# Callisto_Teknic_MSO_PBx4_v1p3.net
KiCad netlist of a schematic drawn in EAGLE
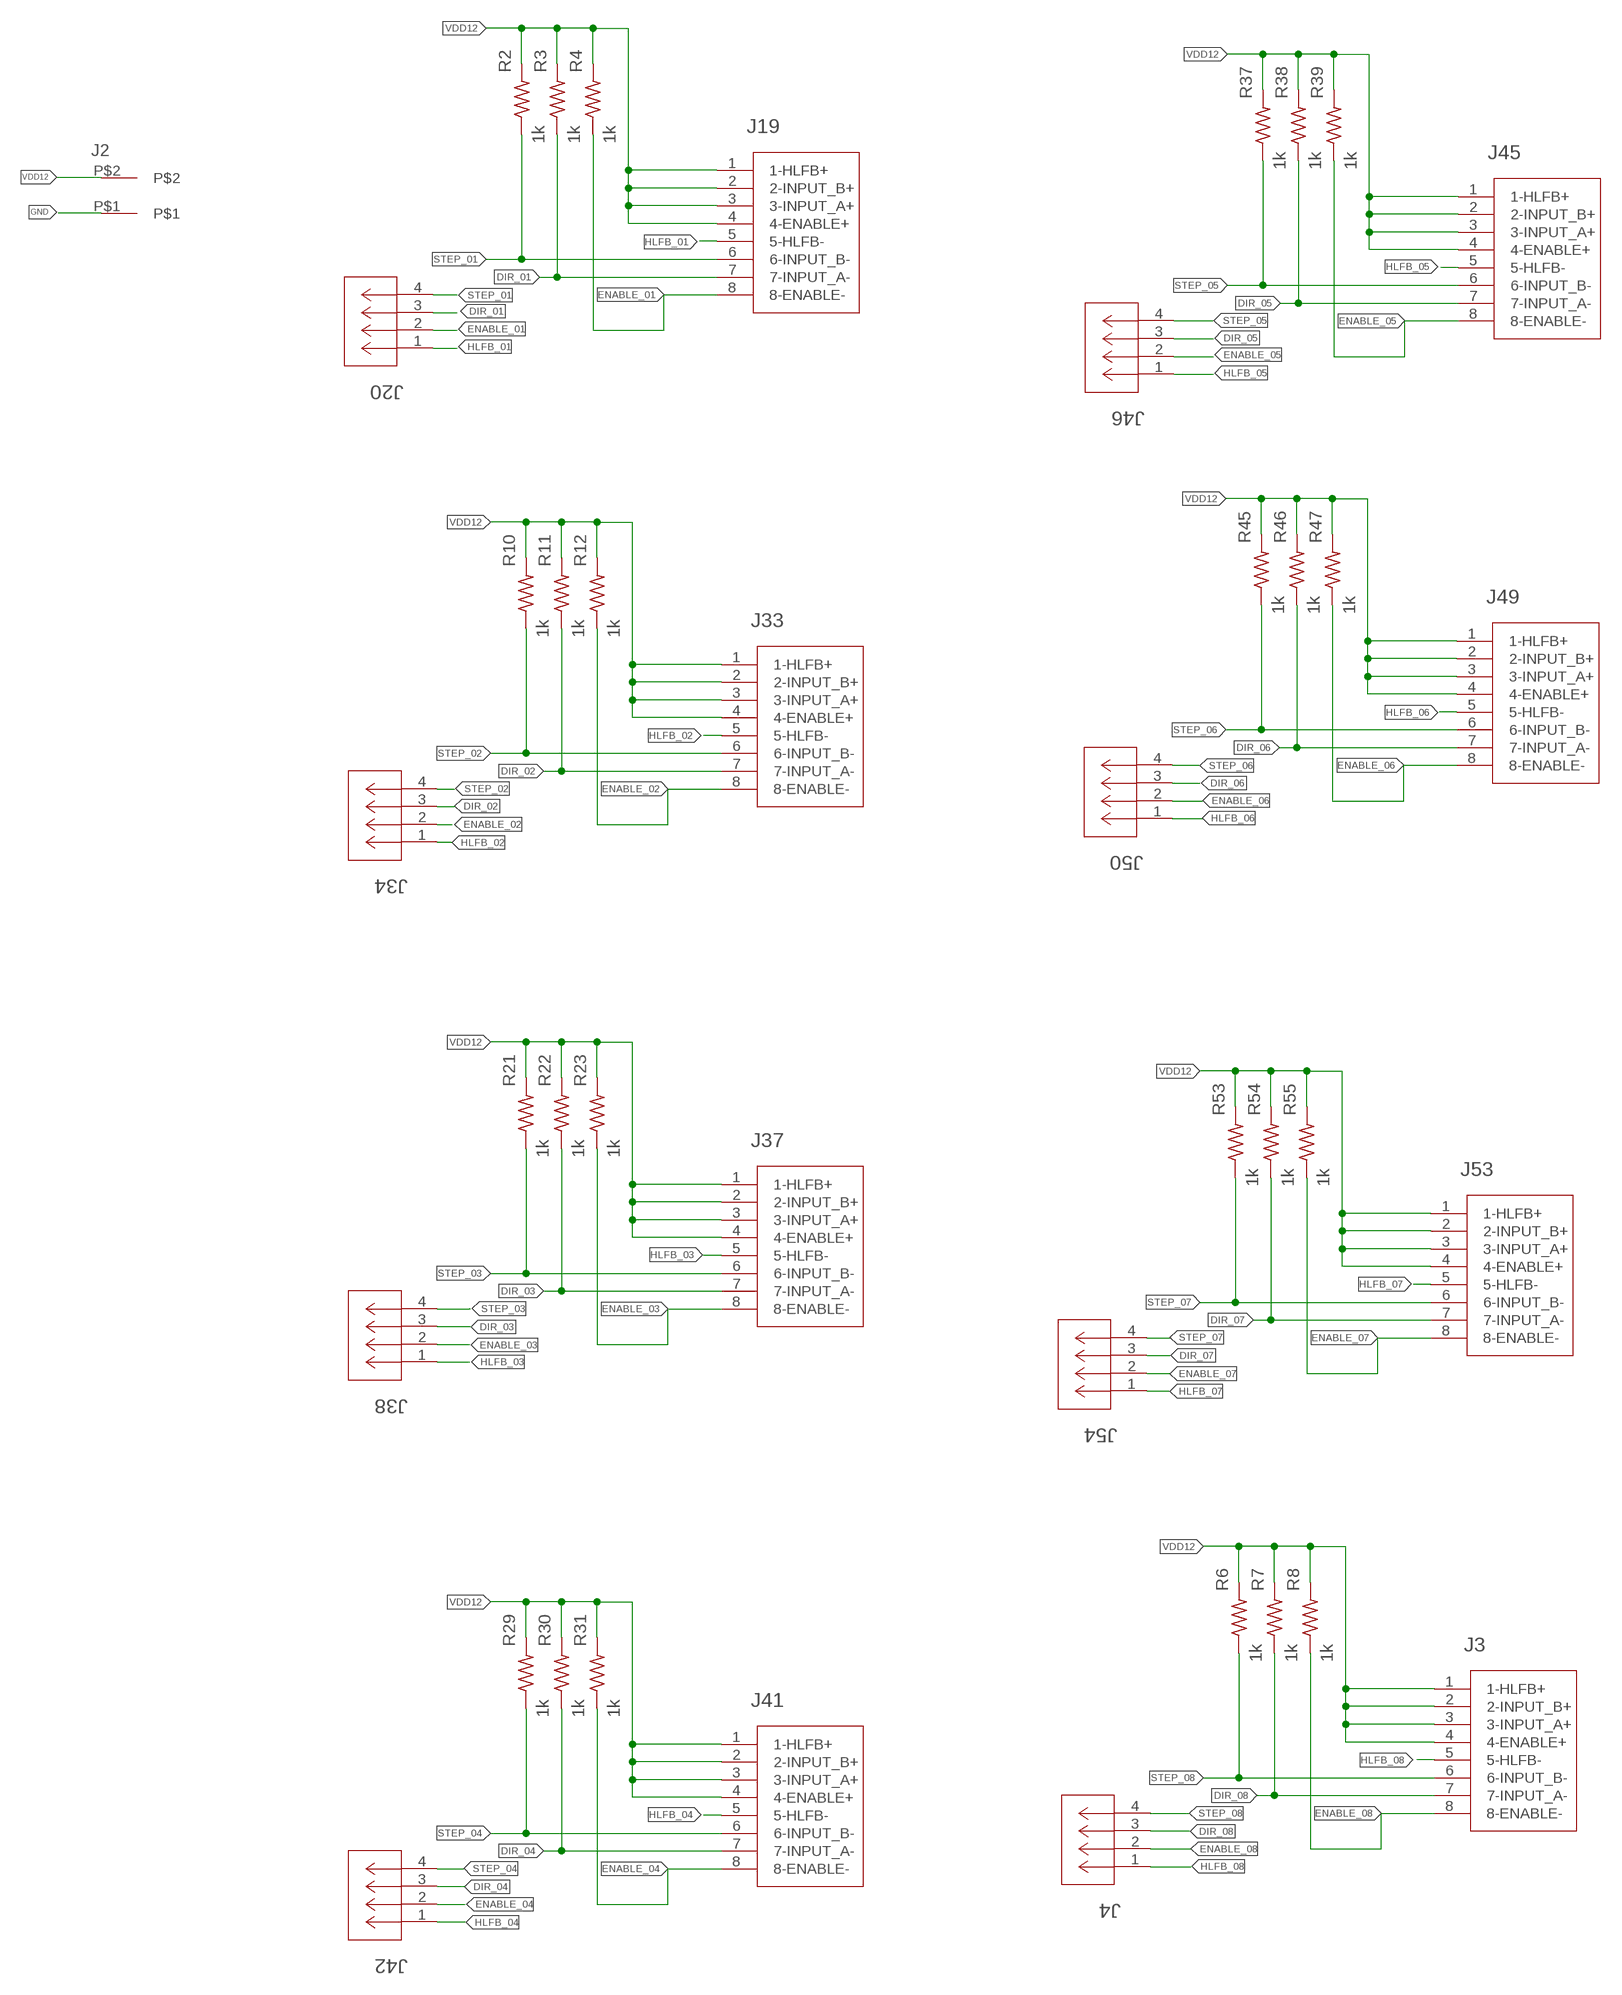
[diagram p0: schematic, sheet 1]

(export (version "E")
  (design (tool "Eeschema 10.0.6"))
  (components
    (comp (ref "J2")
      (value "2-pos")
      (footprint "eagle-import:2_3.81MM_PITCH")
      (fields (field (name "PARTNO") "691322310002"))
      (libsource (lib "eagle-import") (part "3.81MM_1_X_2_RT_ANGLE_PLUG_HEADER"))
    )
    (comp (ref "J3")
      (value "TEKNIC_8PIN_MOTOR")
      (footprint "eagle-import:CON_39281083")
      (fields
        (field (name "MANUFACTURER_PART_NUMBER") "39281083")
        (field (name "COPYRIGHT") "Copyright (C) 2022 Ultra Librarian. All rights reserved.")
      )
      (libsource (lib "eagle-import") (part "TEKNIC_8PIN_MOTOR"))
    )
    (comp (ref "J4")
      (value "CONN_530470410_PICOBLADE_X_4")
      (footprint "eagle-import:CON_530470410_MOL")
      (fields
        (field (name "MANUFACTURER_PART_NUMBER") "530470410")
        (field (name "COPYRIGHT") "Copyright (C) 2022 Ultra Librarian. All rights reserved.")
      )
      (libsource (lib "eagle-import") (part "CONN_530470410_PICOBLADE_X_4"))
    )
    (comp (ref "J19")
      (value "TEKNIC_8PIN_MOTOR")
      (footprint "eagle-import:CON_39281083")
      (fields
        (field (name "MANUFACTURER_PART_NUMBER") "39281083")
        (field (name "COPYRIGHT") "Copyright (C) 2022 Ultra Librarian. All rights reserved.")
      )
      (libsource (lib "eagle-import") (part "TEKNIC_8PIN_MOTOR"))
    )
    (comp (ref "J20")
      (value "CONN_530470410_PICOBLADE_X_4")
      (footprint "eagle-import:CON_530470410_MOL")
      (fields
        (field (name "MANUFACTURER_PART_NUMBER") "530470410")
        (field (name "COPYRIGHT") "Copyright (C) 2022 Ultra Librarian. All rights reserved.")
      )
      (libsource (lib "eagle-import") (part "CONN_530470410_PICOBLADE_X_4"))
    )
    (comp (ref "J33")
      (value "TEKNIC_8PIN_MOTOR")
      (footprint "eagle-import:CON_39281083")
      (fields
        (field (name "MANUFACTURER_PART_NUMBER") "39281083")
        (field (name "COPYRIGHT") "Copyright (C) 2022 Ultra Librarian. All rights reserved.")
      )
      (libsource (lib "eagle-import") (part "TEKNIC_8PIN_MOTOR"))
    )
    (comp (ref "J34")
      (value "CONN_530470410_PICOBLADE_X_4")
      (footprint "eagle-import:CON_530470410_MOL")
      (fields
        (field (name "MANUFACTURER_PART_NUMBER") "530470410")
        (field (name "COPYRIGHT") "Copyright (C) 2022 Ultra Librarian. All rights reserved.")
      )
      (libsource (lib "eagle-import") (part "CONN_530470410_PICOBLADE_X_4"))
    )
    (comp (ref "J37")
      (value "TEKNIC_8PIN_MOTOR")
      (footprint "eagle-import:CON_39281083")
      (fields
        (field (name "MANUFACTURER_PART_NUMBER") "39281083")
        (field (name "COPYRIGHT") "Copyright (C) 2022 Ultra Librarian. All rights reserved.")
      )
      (libsource (lib "eagle-import") (part "TEKNIC_8PIN_MOTOR"))
    )
    (comp (ref "J38")
      (value "CONN_530470410_PICOBLADE_X_4")
      (footprint "eagle-import:CON_530470410_MOL")
      (fields
        (field (name "MANUFACTURER_PART_NUMBER") "530470410")
        (field (name "COPYRIGHT") "Copyright (C) 2022 Ultra Librarian. All rights reserved.")
      )
      (libsource (lib "eagle-import") (part "CONN_530470410_PICOBLADE_X_4"))
    )
    (comp (ref "J41")
      (value "TEKNIC_8PIN_MOTOR")
      (footprint "eagle-import:CON_39281083")
      (fields
        (field (name "MANUFACTURER_PART_NUMBER") "39281083")
        (field (name "COPYRIGHT") "Copyright (C) 2022 Ultra Librarian. All rights reserved.")
      )
      (libsource (lib "eagle-import") (part "TEKNIC_8PIN_MOTOR"))
    )
    (comp (ref "J42")
      (value "CONN_530470410_PICOBLADE_X_4")
      (footprint "eagle-import:CON_530470410_MOL")
      (fields
        (field (name "MANUFACTURER_PART_NUMBER") "530470410")
        (field (name "COPYRIGHT") "Copyright (C) 2022 Ultra Librarian. All rights reserved.")
      )
      (libsource (lib "eagle-import") (part "CONN_530470410_PICOBLADE_X_4"))
    )
    (comp (ref "J45")
      (value "TEKNIC_8PIN_MOTOR")
      (footprint "eagle-import:CON_39281083")
      (fields
        (field (name "MANUFACTURER_PART_NUMBER") "39281083")
        (field (name "COPYRIGHT") "Copyright (C) 2022 Ultra Librarian. All rights reserved.")
      )
      (libsource (lib "eagle-import") (part "TEKNIC_8PIN_MOTOR"))
    )
    (comp (ref "J46")
      (value "CONN_530470410_PICOBLADE_X_4")
      (footprint "eagle-import:CON_530470410_MOL")
      (fields
        (field (name "MANUFACTURER_PART_NUMBER") "530470410")
        (field (name "COPYRIGHT") "Copyright (C) 2022 Ultra Librarian. All rights reserved.")
      )
      (libsource (lib "eagle-import") (part "CONN_530470410_PICOBLADE_X_4"))
    )
    (comp (ref "J49")
      (value "TEKNIC_8PIN_MOTOR")
      (footprint "eagle-import:CON_39281083")
      (fields
        (field (name "MANUFACTURER_PART_NUMBER") "39281083")
        (field (name "COPYRIGHT") "Copyright (C) 2022 Ultra Librarian. All rights reserved.")
      )
      (libsource (lib "eagle-import") (part "TEKNIC_8PIN_MOTOR"))
    )
    (comp (ref "J50")
      (value "CONN_530470410_PICOBLADE_X_4")
      (footprint "eagle-import:CON_530470410_MOL")
      (fields
        (field (name "MANUFACTURER_PART_NUMBER") "530470410")
        (field (name "COPYRIGHT") "Copyright (C) 2022 Ultra Librarian. All rights reserved.")
      )
      (libsource (lib "eagle-import") (part "CONN_530470410_PICOBLADE_X_4"))
    )
    (comp (ref "J53")
      (value "TEKNIC_8PIN_MOTOR")
      (footprint "eagle-import:CON_39281083")
      (fields
        (field (name "MANUFACTURER_PART_NUMBER") "39281083")
        (field (name "COPYRIGHT") "Copyright (C) 2022 Ultra Librarian. All rights reserved.")
      )
      (libsource (lib "eagle-import") (part "TEKNIC_8PIN_MOTOR"))
    )
    (comp (ref "J54")
      (value "CONN_530470410_PICOBLADE_X_4")
      (footprint "eagle-import:CON_530470410_MOL")
      (fields
        (field (name "MANUFACTURER_PART_NUMBER") "530470410")
        (field (name "COPYRIGHT") "Copyright (C) 2022 Ultra Librarian. All rights reserved.")
      )
      (libsource (lib "eagle-import") (part "CONN_530470410_PICOBLADE_X_4"))
    )
    (comp (ref "R2")
      (value "1k")
      (footprint "eagle-import:0805")
      (libsource (lib "eagle-import") (part "R_0805"))
    )
    (comp (ref "R3")
      (value "1k")
      (footprint "eagle-import:0805")
      (libsource (lib "eagle-import") (part "R_0805"))
    )
    (comp (ref "R4")
      (value "1k")
      (footprint "eagle-import:0805")
      (libsource (lib "eagle-import") (part "R_0805"))
    )
    (comp (ref "R6")
      (value "1k")
      (footprint "eagle-import:0805")
      (libsource (lib "eagle-import") (part "R_0805"))
    )
    (comp (ref "R7")
      (value "1k")
      (footprint "eagle-import:0805")
      (libsource (lib "eagle-import") (part "R_0805"))
    )
    (comp (ref "R8")
      (value "1k")
      (footprint "eagle-import:0805")
      (libsource (lib "eagle-import") (part "R_0805"))
    )
    (comp (ref "R10")
      (value "1k")
      (footprint "eagle-import:0805")
      (libsource (lib "eagle-import") (part "R_0805"))
    )
    (comp (ref "R11")
      (value "1k")
      (footprint "eagle-import:0805")
      (libsource (lib "eagle-import") (part "R_0805"))
    )
    (comp (ref "R12")
      (value "1k")
      (footprint "eagle-import:0805")
      (libsource (lib "eagle-import") (part "R_0805"))
    )
    (comp (ref "R21")
      (value "1k")
      (footprint "eagle-import:0805")
      (libsource (lib "eagle-import") (part "R_0805"))
    )
    (comp (ref "R22")
      (value "1k")
      (footprint "eagle-import:0805")
      (libsource (lib "eagle-import") (part "R_0805"))
    )
    (comp (ref "R23")
      (value "1k")
      (footprint "eagle-import:0805")
      (libsource (lib "eagle-import") (part "R_0805"))
    )
    (comp (ref "R29")
      (value "1k")
      (footprint "eagle-import:0805")
      (libsource (lib "eagle-import") (part "R_0805"))
    )
    (comp (ref "R30")
      (value "1k")
      (footprint "eagle-import:0805")
      (libsource (lib "eagle-import") (part "R_0805"))
    )
    (comp (ref "R31")
      (value "1k")
      (footprint "eagle-import:0805")
      (libsource (lib "eagle-import") (part "R_0805"))
    )
    (comp (ref "R37")
      (value "1k")
      (footprint "eagle-import:0805")
      (libsource (lib "eagle-import") (part "R_0805"))
    )
    (comp (ref "R38")
      (value "1k")
      (footprint "eagle-import:0805")
      (libsource (lib "eagle-import") (part "R_0805"))
    )
    (comp (ref "R39")
      (value "1k")
      (footprint "eagle-import:0805")
      (libsource (lib "eagle-import") (part "R_0805"))
    )
    (comp (ref "R45")
      (value "1k")
      (footprint "eagle-import:0805")
      (libsource (lib "eagle-import") (part "R_0805"))
    )
    (comp (ref "R46")
      (value "1k")
      (footprint "eagle-import:0805")
      (libsource (lib "eagle-import") (part "R_0805"))
    )
    (comp (ref "R47")
      (value "1k")
      (footprint "eagle-import:0805")
      (libsource (lib "eagle-import") (part "R_0805"))
    )
    (comp (ref "R53")
      (value "1k")
      (footprint "eagle-import:0805")
      (libsource (lib "eagle-import") (part "R_0805"))
    )
    (comp (ref "R54")
      (value "1k")
      (footprint "eagle-import:0805")
      (libsource (lib "eagle-import") (part "R_0805"))
    )
    (comp (ref "R55")
      (value "1k")
      (footprint "eagle-import:0805")
      (libsource (lib "eagle-import") (part "R_0805"))
    )
  )
  (nets
    (net (code "1") (name "DIR_01") (class "Default")
      (node (ref "J19") (pin "7") (pinfunction "7-INPUT_A-_7") (pintype "passive"))
      (node (ref "J20") (pin "3") (pinfunction "3_3") (pintype "passive"))
      (node (ref "R3") (pin "1") (pinfunction "1_1") (pintype "passive"))
    )
    (net (code "2") (name "DIR_02") (class "Default")
      (node (ref "J33") (pin "7") (pinfunction "7-INPUT_A-_7") (pintype "passive"))
      (node (ref "J34") (pin "3") (pinfunction "3_3") (pintype "passive"))
      (node (ref "R11") (pin "1") (pinfunction "1_1") (pintype "passive"))
    )
    (net (code "3") (name "DIR_03") (class "Default")
      (node (ref "J37") (pin "7") (pinfunction "7-INPUT_A-_7") (pintype "passive"))
      (node (ref "J38") (pin "3") (pinfunction "3_3") (pintype "passive"))
      (node (ref "R22") (pin "1") (pinfunction "1_1") (pintype "passive"))
    )
    (net (code "4") (name "DIR_04") (class "Default")
      (node (ref "J41") (pin "7") (pinfunction "7-INPUT_A-_7") (pintype "passive"))
      (node (ref "J42") (pin "3") (pinfunction "3_3") (pintype "passive"))
      (node (ref "R30") (pin "1") (pinfunction "1_1") (pintype "passive"))
    )
    (net (code "5") (name "DIR_05") (class "Default")
      (node (ref "J45") (pin "7") (pinfunction "7-INPUT_A-_7") (pintype "passive"))
      (node (ref "J46") (pin "3") (pinfunction "3_3") (pintype "passive"))
      (node (ref "R38") (pin "1") (pinfunction "1_1") (pintype "passive"))
    )
    (net (code "6") (name "DIR_06") (class "Default")
      (node (ref "J49") (pin "7") (pinfunction "7-INPUT_A-_7") (pintype "passive"))
      (node (ref "J50") (pin "3") (pinfunction "3_3") (pintype "passive"))
      (node (ref "R46") (pin "1") (pinfunction "1_1") (pintype "passive"))
    )
    (net (code "7") (name "DIR_07") (class "Default")
      (node (ref "J53") (pin "7") (pinfunction "7-INPUT_A-_7") (pintype "passive"))
      (node (ref "J54") (pin "3") (pinfunction "3_3") (pintype "passive"))
      (node (ref "R54") (pin "1") (pinfunction "1_1") (pintype "passive"))
    )
    (net (code "8") (name "DIR_08") (class "Default")
      (node (ref "J3") (pin "7") (pinfunction "7-INPUT_A-_7") (pintype "passive"))
      (node (ref "J4") (pin "3") (pinfunction "3_3") (pintype "passive"))
      (node (ref "R7") (pin "1") (pinfunction "1_1") (pintype "passive"))
    )
    (net (code "9") (name "ENABLE_01") (class "Default")
      (node (ref "J19") (pin "8") (pinfunction "8-ENABLE-_8") (pintype "passive"))
      (node (ref "J20") (pin "2") (pinfunction "2_2") (pintype "passive"))
      (node (ref "R4") (pin "1") (pinfunction "1_1") (pintype "passive"))
    )
    (net (code "10") (name "ENABLE_02") (class "Default")
      (node (ref "J33") (pin "8") (pinfunction "8-ENABLE-_8") (pintype "passive"))
      (node (ref "J34") (pin "2") (pinfunction "2_2") (pintype "passive"))
      (node (ref "R12") (pin "1") (pinfunction "1_1") (pintype "passive"))
    )
    (net (code "11") (name "ENABLE_03") (class "Default")
      (node (ref "J37") (pin "8") (pinfunction "8-ENABLE-_8") (pintype "passive"))
      (node (ref "J38") (pin "2") (pinfunction "2_2") (pintype "passive"))
      (node (ref "R23") (pin "1") (pinfunction "1_1") (pintype "passive"))
    )
    (net (code "12") (name "ENABLE_04") (class "Default")
      (node (ref "J41") (pin "8") (pinfunction "8-ENABLE-_8") (pintype "passive"))
      (node (ref "J42") (pin "2") (pinfunction "2_2") (pintype "passive"))
      (node (ref "R31") (pin "1") (pinfunction "1_1") (pintype "passive"))
    )
    (net (code "13") (name "ENABLE_05") (class "Default")
      (node (ref "J45") (pin "8") (pinfunction "8-ENABLE-_8") (pintype "passive"))
      (node (ref "J46") (pin "2") (pinfunction "2_2") (pintype "passive"))
      (node (ref "R39") (pin "1") (pinfunction "1_1") (pintype "passive"))
    )
    (net (code "14") (name "ENABLE_06") (class "Default")
      (node (ref "J49") (pin "8") (pinfunction "8-ENABLE-_8") (pintype "passive"))
      (node (ref "J50") (pin "2") (pinfunction "2_2") (pintype "passive"))
      (node (ref "R47") (pin "1") (pinfunction "1_1") (pintype "passive"))
    )
    (net (code "15") (name "ENABLE_07") (class "Default")
      (node (ref "J53") (pin "8") (pinfunction "8-ENABLE-_8") (pintype "passive"))
      (node (ref "J54") (pin "2") (pinfunction "2_2") (pintype "passive"))
      (node (ref "R55") (pin "1") (pinfunction "1_1") (pintype "passive"))
    )
    (net (code "16") (name "ENABLE_08") (class "Default")
      (node (ref "J3") (pin "8") (pinfunction "8-ENABLE-_8") (pintype "passive"))
      (node (ref "J4") (pin "2") (pinfunction "2_2") (pintype "passive"))
      (node (ref "R8") (pin "1") (pinfunction "1_1") (pintype "passive"))
    )
    (net (code "17") (name "GND") (class "Default")
      (node (ref "J2") (pin "P$1") (pinfunction "P$1_P$1") (pintype "bidirectional"))
    )
    (net (code "18") (name "HLFB_01") (class "Default")
      (node (ref "J19") (pin "5") (pinfunction "5-HLFB-_5") (pintype "passive"))
      (node (ref "J20") (pin "1") (pinfunction "1_1") (pintype "passive"))
    )
    (net (code "19") (name "HLFB_02") (class "Default")
      (node (ref "J33") (pin "5") (pinfunction "5-HLFB-_5") (pintype "passive"))
      (node (ref "J34") (pin "1") (pinfunction "1_1") (pintype "passive"))
    )
    (net (code "20") (name "HLFB_03") (class "Default")
      (node (ref "J37") (pin "5") (pinfunction "5-HLFB-_5") (pintype "passive"))
      (node (ref "J38") (pin "1") (pinfunction "1_1") (pintype "passive"))
    )
    (net (code "21") (name "HLFB_04") (class "Default")
      (node (ref "J41") (pin "5") (pinfunction "5-HLFB-_5") (pintype "passive"))
      (node (ref "J42") (pin "1") (pinfunction "1_1") (pintype "passive"))
    )
    (net (code "22") (name "HLFB_05") (class "Default")
      (node (ref "J45") (pin "5") (pinfunction "5-HLFB-_5") (pintype "passive"))
      (node (ref "J46") (pin "1") (pinfunction "1_1") (pintype "passive"))
    )
    (net (code "23") (name "HLFB_06") (class "Default")
      (node (ref "J49") (pin "5") (pinfunction "5-HLFB-_5") (pintype "passive"))
      (node (ref "J50") (pin "1") (pinfunction "1_1") (pintype "passive"))
    )
    (net (code "24") (name "HLFB_07") (class "Default")
      (node (ref "J53") (pin "5") (pinfunction "5-HLFB-_5") (pintype "passive"))
      (node (ref "J54") (pin "1") (pinfunction "1_1") (pintype "passive"))
    )
    (net (code "25") (name "HLFB_08") (class "Default")
      (node (ref "J3") (pin "5") (pinfunction "5-HLFB-_5") (pintype "passive"))
      (node (ref "J4") (pin "1") (pinfunction "1_1") (pintype "passive"))
    )
    (net (code "26") (name "STEP_01") (class "Default")
      (node (ref "J19") (pin "6") (pinfunction "6-INPUT_B-_6") (pintype "passive"))
      (node (ref "J20") (pin "4") (pinfunction "4_4") (pintype "passive"))
      (node (ref "R2") (pin "1") (pinfunction "1_1") (pintype "passive"))
    )
    (net (code "27") (name "STEP_02") (class "Default")
      (node (ref "J33") (pin "6") (pinfunction "6-INPUT_B-_6") (pintype "passive"))
      (node (ref "J34") (pin "4") (pinfunction "4_4") (pintype "passive"))
      (node (ref "R10") (pin "1") (pinfunction "1_1") (pintype "passive"))
    )
    (net (code "28") (name "STEP_03") (class "Default")
      (node (ref "J37") (pin "6") (pinfunction "6-INPUT_B-_6") (pintype "passive"))
      (node (ref "J38") (pin "4") (pinfunction "4_4") (pintype "passive"))
      (node (ref "R21") (pin "1") (pinfunction "1_1") (pintype "passive"))
    )
    (net (code "29") (name "STEP_04") (class "Default")
      (node (ref "J41") (pin "6") (pinfunction "6-INPUT_B-_6") (pintype "passive"))
      (node (ref "J42") (pin "4") (pinfunction "4_4") (pintype "passive"))
      (node (ref "R29") (pin "1") (pinfunction "1_1") (pintype "passive"))
    )
    (net (code "30") (name "STEP_05") (class "Default")
      (node (ref "J45") (pin "6") (pinfunction "6-INPUT_B-_6") (pintype "passive"))
      (node (ref "J46") (pin "4") (pinfunction "4_4") (pintype "passive"))
      (node (ref "R37") (pin "1") (pinfunction "1_1") (pintype "passive"))
    )
    (net (code "31") (name "STEP_06") (class "Default")
      (node (ref "J49") (pin "6") (pinfunction "6-INPUT_B-_6") (pintype "passive"))
      (node (ref "J50") (pin "4") (pinfunction "4_4") (pintype "passive"))
      (node (ref "R45") (pin "1") (pinfunction "1_1") (pintype "passive"))
    )
    (net (code "32") (name "STEP_07") (class "Default")
      (node (ref "J53") (pin "6") (pinfunction "6-INPUT_B-_6") (pintype "passive"))
      (node (ref "J54") (pin "4") (pinfunction "4_4") (pintype "passive"))
      (node (ref "R53") (pin "1") (pinfunction "1_1") (pintype "passive"))
    )
    (net (code "33") (name "STEP_08") (class "Default")
      (node (ref "J3") (pin "6") (pinfunction "6-INPUT_B-_6") (pintype "passive"))
      (node (ref "J4") (pin "4") (pinfunction "4_4") (pintype "passive"))
      (node (ref "R6") (pin "1") (pinfunction "1_1") (pintype "passive"))
    )
    (net (code "34") (name "VDD12") (class "Default")
      (node (ref "J19") (pin "1") (pinfunction "1-HLFB+_1") (pintype "passive"))
      (node (ref "J19") (pin "2") (pinfunction "2-INPUT_B+_2") (pintype "passive"))
      (node (ref "J19") (pin "3") (pinfunction "3-INPUT_A+_3") (pintype "passive"))
      (node (ref "J19") (pin "4") (pinfunction "4-ENABLE+_4") (pintype "passive"))
      (node (ref "J2") (pin "P$2") (pinfunction "P$2_P$2") (pintype "bidirectional"))
      (node (ref "J3") (pin "1") (pinfunction "1-HLFB+_1") (pintype "passive"))
      (node (ref "J3") (pin "2") (pinfunction "2-INPUT_B+_2") (pintype "passive"))
      (node (ref "J3") (pin "3") (pinfunction "3-INPUT_A+_3") (pintype "passive"))
      (node (ref "J3") (pin "4") (pinfunction "4-ENABLE+_4") (pintype "passive"))
      (node (ref "J33") (pin "1") (pinfunction "1-HLFB+_1") (pintype "passive"))
      (node (ref "J33") (pin "2") (pinfunction "2-INPUT_B+_2") (pintype "passive"))
      (node (ref "J33") (pin "3") (pinfunction "3-INPUT_A+_3") (pintype "passive"))
      (node (ref "J33") (pin "4") (pinfunction "4-ENABLE+_4") (pintype "passive"))
      (node (ref "J37") (pin "1") (pinfunction "1-HLFB+_1") (pintype "passive"))
      (node (ref "J37") (pin "2") (pinfunction "2-INPUT_B+_2") (pintype "passive"))
      (node (ref "J37") (pin "3") (pinfunction "3-INPUT_A+_3") (pintype "passive"))
      (node (ref "J37") (pin "4") (pinfunction "4-ENABLE+_4") (pintype "passive"))
      (node (ref "J41") (pin "1") (pinfunction "1-HLFB+_1") (pintype "passive"))
      (node (ref "J41") (pin "2") (pinfunction "2-INPUT_B+_2") (pintype "passive"))
      (node (ref "J41") (pin "3") (pinfunction "3-INPUT_A+_3") (pintype "passive"))
      (node (ref "J41") (pin "4") (pinfunction "4-ENABLE+_4") (pintype "passive"))
      (node (ref "J45") (pin "1") (pinfunction "1-HLFB+_1") (pintype "passive"))
      (node (ref "J45") (pin "2") (pinfunction "2-INPUT_B+_2") (pintype "passive"))
      (node (ref "J45") (pin "3") (pinfunction "3-INPUT_A+_3") (pintype "passive"))
      (node (ref "J45") (pin "4") (pinfunction "4-ENABLE+_4") (pintype "passive"))
      (node (ref "J49") (pin "1") (pinfunction "1-HLFB+_1") (pintype "passive"))
      (node (ref "J49") (pin "2") (pinfunction "2-INPUT_B+_2") (pintype "passive"))
      (node (ref "J49") (pin "3") (pinfunction "3-INPUT_A+_3") (pintype "passive"))
      (node (ref "J49") (pin "4") (pinfunction "4-ENABLE+_4") (pintype "passive"))
      (node (ref "J53") (pin "1") (pinfunction "1-HLFB+_1") (pintype "passive"))
      (node (ref "J53") (pin "2") (pinfunction "2-INPUT_B+_2") (pintype "passive"))
      (node (ref "J53") (pin "3") (pinfunction "3-INPUT_A+_3") (pintype "passive"))
      (node (ref "J53") (pin "4") (pinfunction "4-ENABLE+_4") (pintype "passive"))
      (node (ref "R10") (pin "2") (pinfunction "2_2") (pintype "passive"))
      (node (ref "R11") (pin "2") (pinfunction "2_2") (pintype "passive"))
      (node (ref "R12") (pin "2") (pinfunction "2_2") (pintype "passive"))
      (node (ref "R2") (pin "2") (pinfunction "2_2") (pintype "passive"))
      (node (ref "R21") (pin "2") (pinfunction "2_2") (pintype "passive"))
      (node (ref "R22") (pin "2") (pinfunction "2_2") (pintype "passive"))
      (node (ref "R23") (pin "2") (pinfunction "2_2") (pintype "passive"))
      (node (ref "R29") (pin "2") (pinfunction "2_2") (pintype "passive"))
      (node (ref "R3") (pin "2") (pinfunction "2_2") (pintype "passive"))
      (node (ref "R30") (pin "2") (pinfunction "2_2") (pintype "passive"))
      (node (ref "R31") (pin "2") (pinfunction "2_2") (pintype "passive"))
      (node (ref "R37") (pin "2") (pinfunction "2_2") (pintype "passive"))
      (node (ref "R38") (pin "2") (pinfunction "2_2") (pintype "passive"))
      (node (ref "R39") (pin "2") (pinfunction "2_2") (pintype "passive"))
      (node (ref "R4") (pin "2") (pinfunction "2_2") (pintype "passive"))
      (node (ref "R45") (pin "2") (pinfunction "2_2") (pintype "passive"))
      (node (ref "R46") (pin "2") (pinfunction "2_2") (pintype "passive"))
      (node (ref "R47") (pin "2") (pinfunction "2_2") (pintype "passive"))
      (node (ref "R53") (pin "2") (pinfunction "2_2") (pintype "passive"))
      (node (ref "R54") (pin "2") (pinfunction "2_2") (pintype "passive"))
      (node (ref "R55") (pin "2") (pinfunction "2_2") (pintype "passive"))
      (node (ref "R6") (pin "2") (pinfunction "2_2") (pintype "passive"))
      (node (ref "R7") (pin "2") (pinfunction "2_2") (pintype "passive"))
      (node (ref "R8") (pin "2") (pinfunction "2_2") (pintype "passive"))
    )
  )
)
